# 1_-Controller_Page.net
KiCad netlist of a schematic drawn in Altium Designer
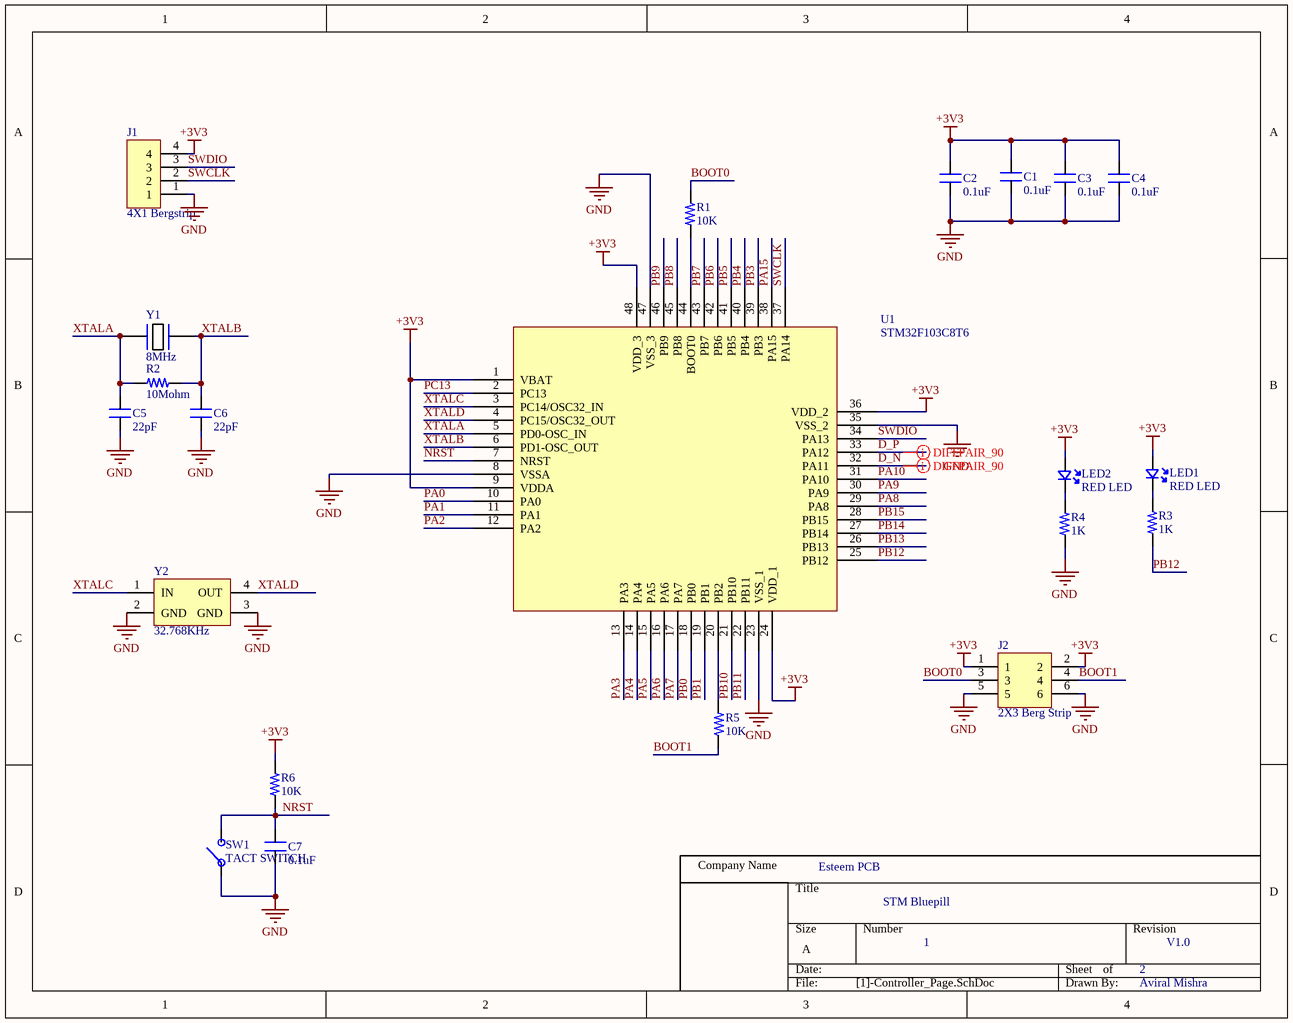
[diagram p0: [1]-Controller_Page.SchDoc]

(export (version "E")
  (design (tool "Eeschema 10.0.6"))
  (components
    (comp (ref "C1")
      (value "0.1uF")
      (footprint "CAP_0805")
      (description "0.1µF ±5% 50V Ceramic Capacitor X7R 0805 (2012 Metric)")
      (fields
        (field (name "MANUFACTURER") "KEMET")
        (field (name "MANUFACTURING PART NUMBER") "C0805C104J5RACTU")
      )
      (libsource (lib "STM_SCH_LIB") (part "CAP_0.1uF-50V-5%-0805"))
    )
    (comp (ref "C2")
      (value "0.1uF")
      (footprint "CAP_0805")
      (description "0.1µF ±5% 50V Ceramic Capacitor X7R 0805 (2012 Metric)")
      (fields
        (field (name "MANUFACTURER") "KEMET")
        (field (name "MANUFACTURING PART NUMBER") "C0805C104J5RACTU")
      )
      (libsource (lib "STM_SCH_LIB") (part "CAP_0.1uF-50V-5%-0805"))
    )
    (comp (ref "C3")
      (value "0.1uF")
      (footprint "CAP_0805")
      (description "0.1µF ±5% 50V Ceramic Capacitor X7R 0805 (2012 Metric)")
      (fields
        (field (name "MANUFACTURER") "KEMET")
        (field (name "MANUFACTURING PART NUMBER") "C0805C104J5RACTU")
      )
      (libsource (lib "STM_SCH_LIB") (part "CAP_0.1uF-50V-5%-0805"))
    )
    (comp (ref "C4")
      (value "0.1uF")
      (footprint "CAP_0805")
      (description "0.1µF ±5% 50V Ceramic Capacitor X7R 0805 (2012 Metric)")
      (fields
        (field (name "MANUFACTURER") "KEMET")
        (field (name "MANUFACTURING PART NUMBER") "C0805C104J5RACTU")
      )
      (libsource (lib "STM_SCH_LIB") (part "CAP_0.1uF-50V-5%-0805"))
    )
    (comp (ref "C5")
      (value "22pF")
      (footprint "CAP_0805")
      (description "22pF ±5% 50V Ceramic Capacitor C0G, NP0 0805 (2012 Metric)")
      (fields
        (field (name "MANUFACTURER") "KEMET")
        (field (name "MANUFACTURER PART NUMBER") "C0805C220J5GACTU")
      )
      (libsource (lib "STM_SCH_LIB") (part "CAP_22pF-50V-5%-0805"))
    )
    (comp (ref "C6")
      (value "22pF")
      (footprint "CAP_0805")
      (description "22pF ±5% 50V Ceramic Capacitor C0G, NP0 0805 (2012 Metric)")
      (fields
        (field (name "MANUFACTURER") "KEMET")
        (field (name "MANUFACTURER PART NUMBER") "C0805C220J5GACTU")
      )
      (libsource (lib "STM_SCH_LIB") (part "CAP_22pF-50V-5%-0805"))
    )
    (comp (ref "C7")
      (value "0.1uF")
      (footprint "CAP_0805")
      (description "0.1µF ±5% 50V Ceramic Capacitor X7R 0805 (2012 Metric)")
      (fields
        (field (name "MANUFACTURER") "KEMET")
        (field (name "MANUFACTURING PART NUMBER") "C0805C104J5RACTU")
      )
      (libsource (lib "STM_SCH_LIB") (part "CAP_0.1uF-50V-5%-0805"))
    )
    (comp (ref "J1")
      (value "4X1 Bergstrip")
      (footprint "CON4_100_40D72_TH_ST_MALE")
      (description "4 pin, 1 row, 2.54mm pitch bergstrip")
      (fields (field (name "MANUFACTURER") "NA"))
      (libsource (lib "STM_SCH_LIB") (part "CON-BS-PLG_4X1-100-TH-ST"))
    )
    (comp (ref "J2")
      (value "2X3 Berg Strip")
      (footprint "CON6_100_59D78_TH_ST_Duplicate")
      (description "6 pin, 2 row, 2.54mm pitch bergstrip")
      (fields (field (name "MANUFACTURER") "NA"))
      (libsource (lib "STM_SCH_LIB") (part "CON-BS-PLG_2X3-100-TH-ST"))
    )
    (comp (ref "LED1")
      (value "RED LED")
      (footprint "LED_0805")
      (description "Red 621nm LED Indication - Discrete 2V 0805 (2012 Metric)")
      (fields
        (field (name "MANUFACTURER") "Lite-On Inc.")
        (field (name "MANUFACTURER PART NUMBER") "LTST-C170EKT")
      )
      (libsource (lib "STM_SCH_LIB") (part "LED-RED_10mA-0805"))
    )
    (comp (ref "LED2")
      (value "RED LED")
      (footprint "LED_0805")
      (description "Red 621nm LED Indication - Discrete 2V 0805 (2012 Metric)")
      (fields
        (field (name "MANUFACTURER") "Lite-On Inc.")
        (field (name "MANUFACTURER PART NUMBER") "LTST-C170EKT")
      )
      (libsource (lib "STM_SCH_LIB") (part "LED-RED_10mA-0805"))
    )
    (comp (ref "R1")
      (value "10K")
      (footprint "RES_0805")
      (description "10 kOhms ±1% 0.125W, 1/8W Chip Resistor 0805 (2012 Metric) Moisture Resistant Thick Film")
      (fields
        (field (name "MANUFACTURER") "Yageo")
        (field (name "MANUFACTURING PART NUMBER") "RC0805FR-0710KL")
      )
      (libsource (lib "STM_SCH_LIB") (part "RES_10K-0.125W-1%-0805"))
    )
    (comp (ref "R2")
      (value "10Mohm")
      (footprint "RES_0805")
      (fields
        (field (name "MANUFACTURER") "Rohm Semiconductor")
        (field (name "MANUFACTURING PART NUMBER") "KTR10EZPF1005")
      )
      (libsource (lib "STM_SCH_LIB") (part "RES_10MOHM-0.125W-1%-0805"))
    )
    (comp (ref "R3")
      (value "1K")
      (footprint "RES_0805")
      (description "1 kOhms ±1% 0.125W, 1/8W Chip Resistor 0805 (2012 Metric) Moisture Resistant Thick Film")
      (fields (field (name "MANUFACTURER") "??á") (field (name "MANUFACTURER PART NUMBER") "RC0805FR-071KL"))
      (libsource (lib "STM_SCH_LIB") (part "RES_1K-0.125W-1%-0805"))
    )
    (comp (ref "R4")
      (value "1K")
      (footprint "RES_0805")
      (description "1 kOhms ±1% 0.125W, 1/8W Chip Resistor 0805 (2012 Metric) Moisture Resistant Thick Film")
      (fields (field (name "MANUFACTURER") "??á") (field (name "MANUFACTURER PART NUMBER") "RC0805FR-071KL"))
      (libsource (lib "STM_SCH_LIB") (part "RES_1K-0.125W-1%-0805"))
    )
    (comp (ref "R5")
      (value "10K")
      (footprint "RES_0805")
      (description "10 kOhms ±1% 0.125W, 1/8W Chip Resistor 0805 (2012 Metric) Moisture Resistant Thick Film")
      (fields
        (field (name "MANUFACTURER") "Yageo")
        (field (name "MANUFACTURING PART NUMBER") "RC0805FR-0710KL")
      )
      (libsource (lib "STM_SCH_LIB") (part "RES_10K-0.125W-1%-0805"))
    )
    (comp (ref "R6")
      (value "10K")
      (footprint "RES_0805")
      (description "10 kOhms ±1% 0.125W, 1/8W Chip Resistor 0805 (2012 Metric) Moisture Resistant Thick Film")
      (fields
        (field (name "MANUFACTURER") "Yageo")
        (field (name "MANUFACTURING PART NUMBER") "RC0805FR-0710KL")
      )
      (libsource (lib "STM_SCH_LIB") (part "RES_10K-0.125W-1%-0805"))
    )
    (comp (ref "SW1")
      (value "TACT SWITCH")
      (footprint "SW_342_SMD")
      (description "Tactile Switch SPST-NO Top Actuated Surface Mount")
      (fields (field (name "MANUFACTURER") "C&K") (field (name "MANUFACTURING PART NUMBER") "KSR223GLFG"))
      (libsource (lib "STM_SCH_LIB") (part "SW_KSR223GLFG-SMD"))
    )
    (comp (ref "U1")
      (value "STM32F103C8T6")
      (footprint "LQFP-48_19.6_393_58X11_SMD")
      (description "ARM® Cortex®-M3 STM32F1 Microcontroller IC 32-Bit 72MHz 64KB (64K x 8) FLASH")
      (fields (field (name "MANUFACTURER") "STMicroelectronics"))
      (libsource (lib "STM_SCH_LIB") (part "IC-STM32F103C8T6 _1"))
    )
    (comp (ref "Y1")
      (value "8MHz")
      (footprint "XTAL_314_240X47_SMD")
      (description "Crystals 8MHz 22pF -20C 70C")
      (fields
        (field (name "MANUFACTURER") "IQD Frequency Products")
        (field (name "MANUFACTURING PART NUMBER") "LFXTAL030234Reel")
      )
      (libsource (lib "STM_SCH_LIB") (part "XTAL_8MHZ-LFXTAL030234"))
    )
    (comp (ref "Y2")
      (value "32.768KHz")
      (footprint "XTAL_MC-405 32.7680K-G3")
      (description "Crystals SMD AT XTL MHZ +/-50PPM 12.5 PF 250 T/R")
      (fields
        (field (name "MANUFACTURER") "Epson")
        (field (name "MANUFACTURING PART NUMBER") "MC-405 32.7680K-G3: ROHS")
      )
      (libsource (lib "STM_SCH_LIB") (part "XTAL_32.768KHz-MC-405 32.7680K-G3"))
    )
  )
  (nets
    (net (code "1") (name "+3V3") (class "Default")
      (node (ref "C1") (pin "2") (pinfunction "2_2") (pintype "passive"))
      (node (ref "C2") (pin "2") (pinfunction "2_2") (pintype "passive"))
      (node (ref "C3") (pin "2") (pinfunction "2_2") (pintype "passive"))
      (node (ref "C4") (pin "2") (pinfunction "2_2") (pintype "passive"))
      (node (ref "J1") (pin "4") (pinfunction "4_4") (pintype "passive"))
      (node (ref "J2") (pin "1") (pinfunction "1_1") (pintype "passive"))
      (node (ref "J2") (pin "2") (pinfunction "2_2") (pintype "passive"))
      (node (ref "LED1") (pin "A") (pinfunction "A_A") (pintype "passive"))
      (node (ref "LED2") (pin "A") (pinfunction "A_A") (pintype "passive"))
      (node (ref "R6") (pin "2") (pinfunction "2_2") (pintype "passive"))
      (node (ref "U1") (pin "1") (pinfunction "VBAT_1") (pintype "passive"))
      (node (ref "U1") (pin "24") (pinfunction "VDD_1_24") (pintype "passive"))
      (node (ref "U1") (pin "36") (pinfunction "VDD_2_36") (pintype "passive"))
      (node (ref "U1") (pin "48") (pinfunction "VDD_3_48") (pintype "passive"))
      (node (ref "U1") (pin "9") (pinfunction "VDDA_9") (pintype "passive"))
    )
    (net (code "2") (name "/BOOT0") (class "Default")
      (node (ref "J2") (pin "3") (pinfunction "3_3") (pintype "passive"))
      (node (ref "R1") (pin "2") (pinfunction "2_2") (pintype "passive"))
    )
    (net (code "3") (name "/BOOT1") (class "Default")
      (node (ref "J2") (pin "4") (pinfunction "4_4") (pintype "passive"))
      (node (ref "R5") (pin "2") (pinfunction "2_2") (pintype "passive"))
    )
    (net (code "4") (name "/D_N") (class "Default")
      (node (ref "U1") (pin "32") (pinfunction "PA11_32") (pintype "passive"))
    )
    (net (code "5") (name "/D_P") (class "Default")
      (node (ref "U1") (pin "33") (pinfunction "PA12_33") (pintype "passive"))
    )
    (net (code "6") (name "/NRST") (class "Default")
      (node (ref "C7") (pin "2") (pinfunction "2_2") (pintype "passive"))
      (node (ref "R6") (pin "1") (pinfunction "1_1") (pintype "passive"))
      (node (ref "SW1") (pin "2") (pinfunction "2_2") (pintype "passive"))
      (node (ref "U1") (pin "7") (pinfunction "NRST_7") (pintype "passive"))
    )
    (net (code "7") (name "/PA0") (class "Default")
      (node (ref "U1") (pin "10") (pinfunction "PA0_10") (pintype "passive"))
    )
    (net (code "8") (name "/PA1") (class "Default")
      (node (ref "U1") (pin "11") (pinfunction "PA1_11") (pintype "passive"))
    )
    (net (code "9") (name "/PA2") (class "Default")
      (node (ref "U1") (pin "12") (pinfunction "PA2_12") (pintype "passive"))
    )
    (net (code "10") (name "/PA3") (class "Default")
      (node (ref "U1") (pin "13") (pinfunction "PA3_13") (pintype "passive"))
    )
    (net (code "11") (name "/PA4") (class "Default")
      (node (ref "U1") (pin "14") (pinfunction "PA4_14") (pintype "passive"))
    )
    (net (code "12") (name "/PA5") (class "Default")
      (node (ref "U1") (pin "15") (pinfunction "PA5_15") (pintype "passive"))
    )
    (net (code "13") (name "/PA6") (class "Default")
      (node (ref "U1") (pin "16") (pinfunction "PA6_16") (pintype "passive"))
    )
    (net (code "14") (name "/PA7") (class "Default")
      (node (ref "U1") (pin "17") (pinfunction "PA7_17") (pintype "passive"))
    )
    (net (code "15") (name "/PA8") (class "Default")
      (node (ref "U1") (pin "29") (pinfunction "PA8_29") (pintype "passive"))
    )
    (net (code "16") (name "/PA9") (class "Default")
      (node (ref "U1") (pin "30") (pinfunction "PA9_30") (pintype "passive"))
    )
    (net (code "17") (name "/PA10") (class "Default")
      (node (ref "U1") (pin "31") (pinfunction "PA10_31") (pintype "passive"))
    )
    (net (code "18") (name "/PA15") (class "Default")
      (node (ref "U1") (pin "38") (pinfunction "PA15_38") (pintype "passive"))
    )
    (net (code "19") (name "/PB0") (class "Default")
      (node (ref "U1") (pin "18") (pinfunction "PB0_18") (pintype "passive"))
    )
    (net (code "20") (name "/PB1") (class "Default")
      (node (ref "U1") (pin "19") (pinfunction "PB1_19") (pintype "passive"))
    )
    (net (code "21") (name "/PB3") (class "Default")
      (node (ref "U1") (pin "39") (pinfunction "PB3_39") (pintype "passive"))
    )
    (net (code "22") (name "/PB4") (class "Default")
      (node (ref "U1") (pin "40") (pinfunction "PB4_40") (pintype "passive"))
    )
    (net (code "23") (name "/PB5") (class "Default")
      (node (ref "U1") (pin "41") (pinfunction "PB5_41") (pintype "passive"))
    )
    (net (code "24") (name "/PB6") (class "Default")
      (node (ref "U1") (pin "42") (pinfunction "PB6_42") (pintype "passive"))
    )
    (net (code "25") (name "/PB7") (class "Default")
      (node (ref "U1") (pin "43") (pinfunction "PB7_43") (pintype "passive"))
    )
    (net (code "26") (name "/PB8") (class "Default")
      (node (ref "U1") (pin "45") (pinfunction "PB8_45") (pintype "passive"))
    )
    (net (code "27") (name "/PB9") (class "Default")
      (node (ref "U1") (pin "46") (pinfunction "PB9_46") (pintype "passive"))
    )
    (net (code "28") (name "/PB10") (class "Default")
      (node (ref "U1") (pin "21") (pinfunction "PB10_21") (pintype "passive"))
    )
    (net (code "29") (name "/PB11") (class "Default")
      (node (ref "U1") (pin "22") (pinfunction "PB11_22") (pintype "passive"))
    )
    (net (code "30") (name "/PB12") (class "Default")
      (node (ref "R3") (pin "1") (pinfunction "1_1") (pintype "passive"))
      (node (ref "U1") (pin "25") (pinfunction "PB12_25") (pintype "passive"))
    )
    (net (code "31") (name "/PB13") (class "Default")
      (node (ref "U1") (pin "26") (pinfunction "PB13_26") (pintype "passive"))
    )
    (net (code "32") (name "/PB14") (class "Default")
      (node (ref "U1") (pin "27") (pinfunction "PB14_27") (pintype "passive"))
    )
    (net (code "33") (name "/PB15") (class "Default")
      (node (ref "U1") (pin "28") (pinfunction "PB15_28") (pintype "passive"))
    )
    (net (code "34") (name "/PC13") (class "Default")
      (node (ref "U1") (pin "2") (pinfunction "PC13_2") (pintype "passive"))
    )
    (net (code "35") (name "/SWCLK") (class "Default")
      (node (ref "J1") (pin "2") (pinfunction "2_2") (pintype "passive"))
      (node (ref "U1") (pin "37") (pinfunction "PA14_37") (pintype "passive"))
    )
    (net (code "36") (name "/SWDIO") (class "Default")
      (node (ref "J1") (pin "3") (pinfunction "3_3") (pintype "passive"))
      (node (ref "U1") (pin "34") (pinfunction "PA13_34") (pintype "passive"))
    )
    (net (code "37") (name "/XTALA") (class "Default")
      (node (ref "C5") (pin "2") (pinfunction "2_2") (pintype "passive"))
      (node (ref "R2") (pin "1") (pinfunction "1_1") (pintype "passive"))
      (node (ref "U1") (pin "5") (pinfunction "PD0-OSC_IN_5") (pintype "passive"))
      (node (ref "Y1") (pin "1") (pinfunction "1_1") (pintype "passive"))
    )
    (net (code "38") (name "/XTALB") (class "Default")
      (node (ref "C6") (pin "2") (pinfunction "2_2") (pintype "passive"))
      (node (ref "R2") (pin "2") (pinfunction "2_2") (pintype "passive"))
      (node (ref "U1") (pin "6") (pinfunction "PD1-OSC_OUT_6") (pintype "passive"))
      (node (ref "Y1") (pin "2") (pinfunction "2_2") (pintype "passive"))
    )
    (net (code "39") (name "/XTALC") (class "Default")
      (node (ref "U1") (pin "3") (pinfunction "PC14/OSC32_IN_3") (pintype "passive"))
      (node (ref "Y2") (pin "1") (pinfunction "IN_1") (pintype "passive"))
    )
    (net (code "40") (name "/XTALD") (class "Default")
      (node (ref "U1") (pin "4") (pinfunction "PC15/OSC32_OUT_4") (pintype "passive"))
      (node (ref "Y2") (pin "4") (pinfunction "OUT_4") (pintype "passive"))
    )
    (net (code "41") (name "GND") (class "Default")
      (node (ref "C1") (pin "1") (pinfunction "1_1") (pintype "passive"))
      (node (ref "C2") (pin "1") (pinfunction "1_1") (pintype "passive"))
      (node (ref "C3") (pin "1") (pinfunction "1_1") (pintype "passive"))
      (node (ref "C4") (pin "1") (pinfunction "1_1") (pintype "passive"))
      (node (ref "C5") (pin "1") (pinfunction "1_1") (pintype "passive"))
      (node (ref "C6") (pin "1") (pinfunction "1_1") (pintype "passive"))
      (node (ref "C7") (pin "1") (pinfunction "1_1") (pintype "passive"))
      (node (ref "J1") (pin "1") (pinfunction "1_1") (pintype "passive"))
      (node (ref "J2") (pin "5") (pinfunction "5_5") (pintype "passive"))
      (node (ref "J2") (pin "6") (pinfunction "6_6") (pintype "passive"))
      (node (ref "R4") (pin "1") (pinfunction "1_1") (pintype "passive"))
      (node (ref "SW1") (pin "1") (pinfunction "1_1") (pintype "passive"))
      (node (ref "U1") (pin "23") (pinfunction "VSS_1_23") (pintype "passive"))
      (node (ref "U1") (pin "35") (pinfunction "VSS_2_35") (pintype "passive"))
      (node (ref "U1") (pin "47") (pinfunction "VSS_3_47") (pintype "passive"))
      (node (ref "U1") (pin "8") (pinfunction "VSSA_8") (pintype "passive"))
      (node (ref "Y2") (pin "2") (pinfunction "GND_2") (pintype "passive"))
      (node (ref "Y2") (pin "3") (pinfunction "GND_3") (pintype "passive"))
    )
    (net (code "42") (name "Net-(LED1-PadK)") (class "Default")
      (node (ref "LED1") (pin "K") (pinfunction "K_K") (pintype "passive"))
      (node (ref "R3") (pin "2") (pinfunction "2_2") (pintype "passive"))
    )
    (net (code "43") (name "Net-(LED2-PadK)") (class "Default")
      (node (ref "LED2") (pin "K") (pinfunction "K_K") (pintype "passive"))
      (node (ref "R4") (pin "2") (pinfunction "2_2") (pintype "passive"))
    )
    (net (code "44") (name "Net-(U1-BOOT0)") (class "Default")
      (node (ref "R1") (pin "1") (pinfunction "1_1") (pintype "passive"))
      (node (ref "U1") (pin "44") (pinfunction "BOOT0_44") (pintype "passive"))
    )
    (net (code "45") (name "Net-(U1-PB2)") (class "Default")
      (node (ref "R5") (pin "1") (pinfunction "1_1") (pintype "passive"))
      (node (ref "U1") (pin "20") (pinfunction "PB2_20") (pintype "passive"))
    )
  )
)
